# 05_LMS7002M_Misc.net
KiCad netlist of a schematic drawn in Altium Designer
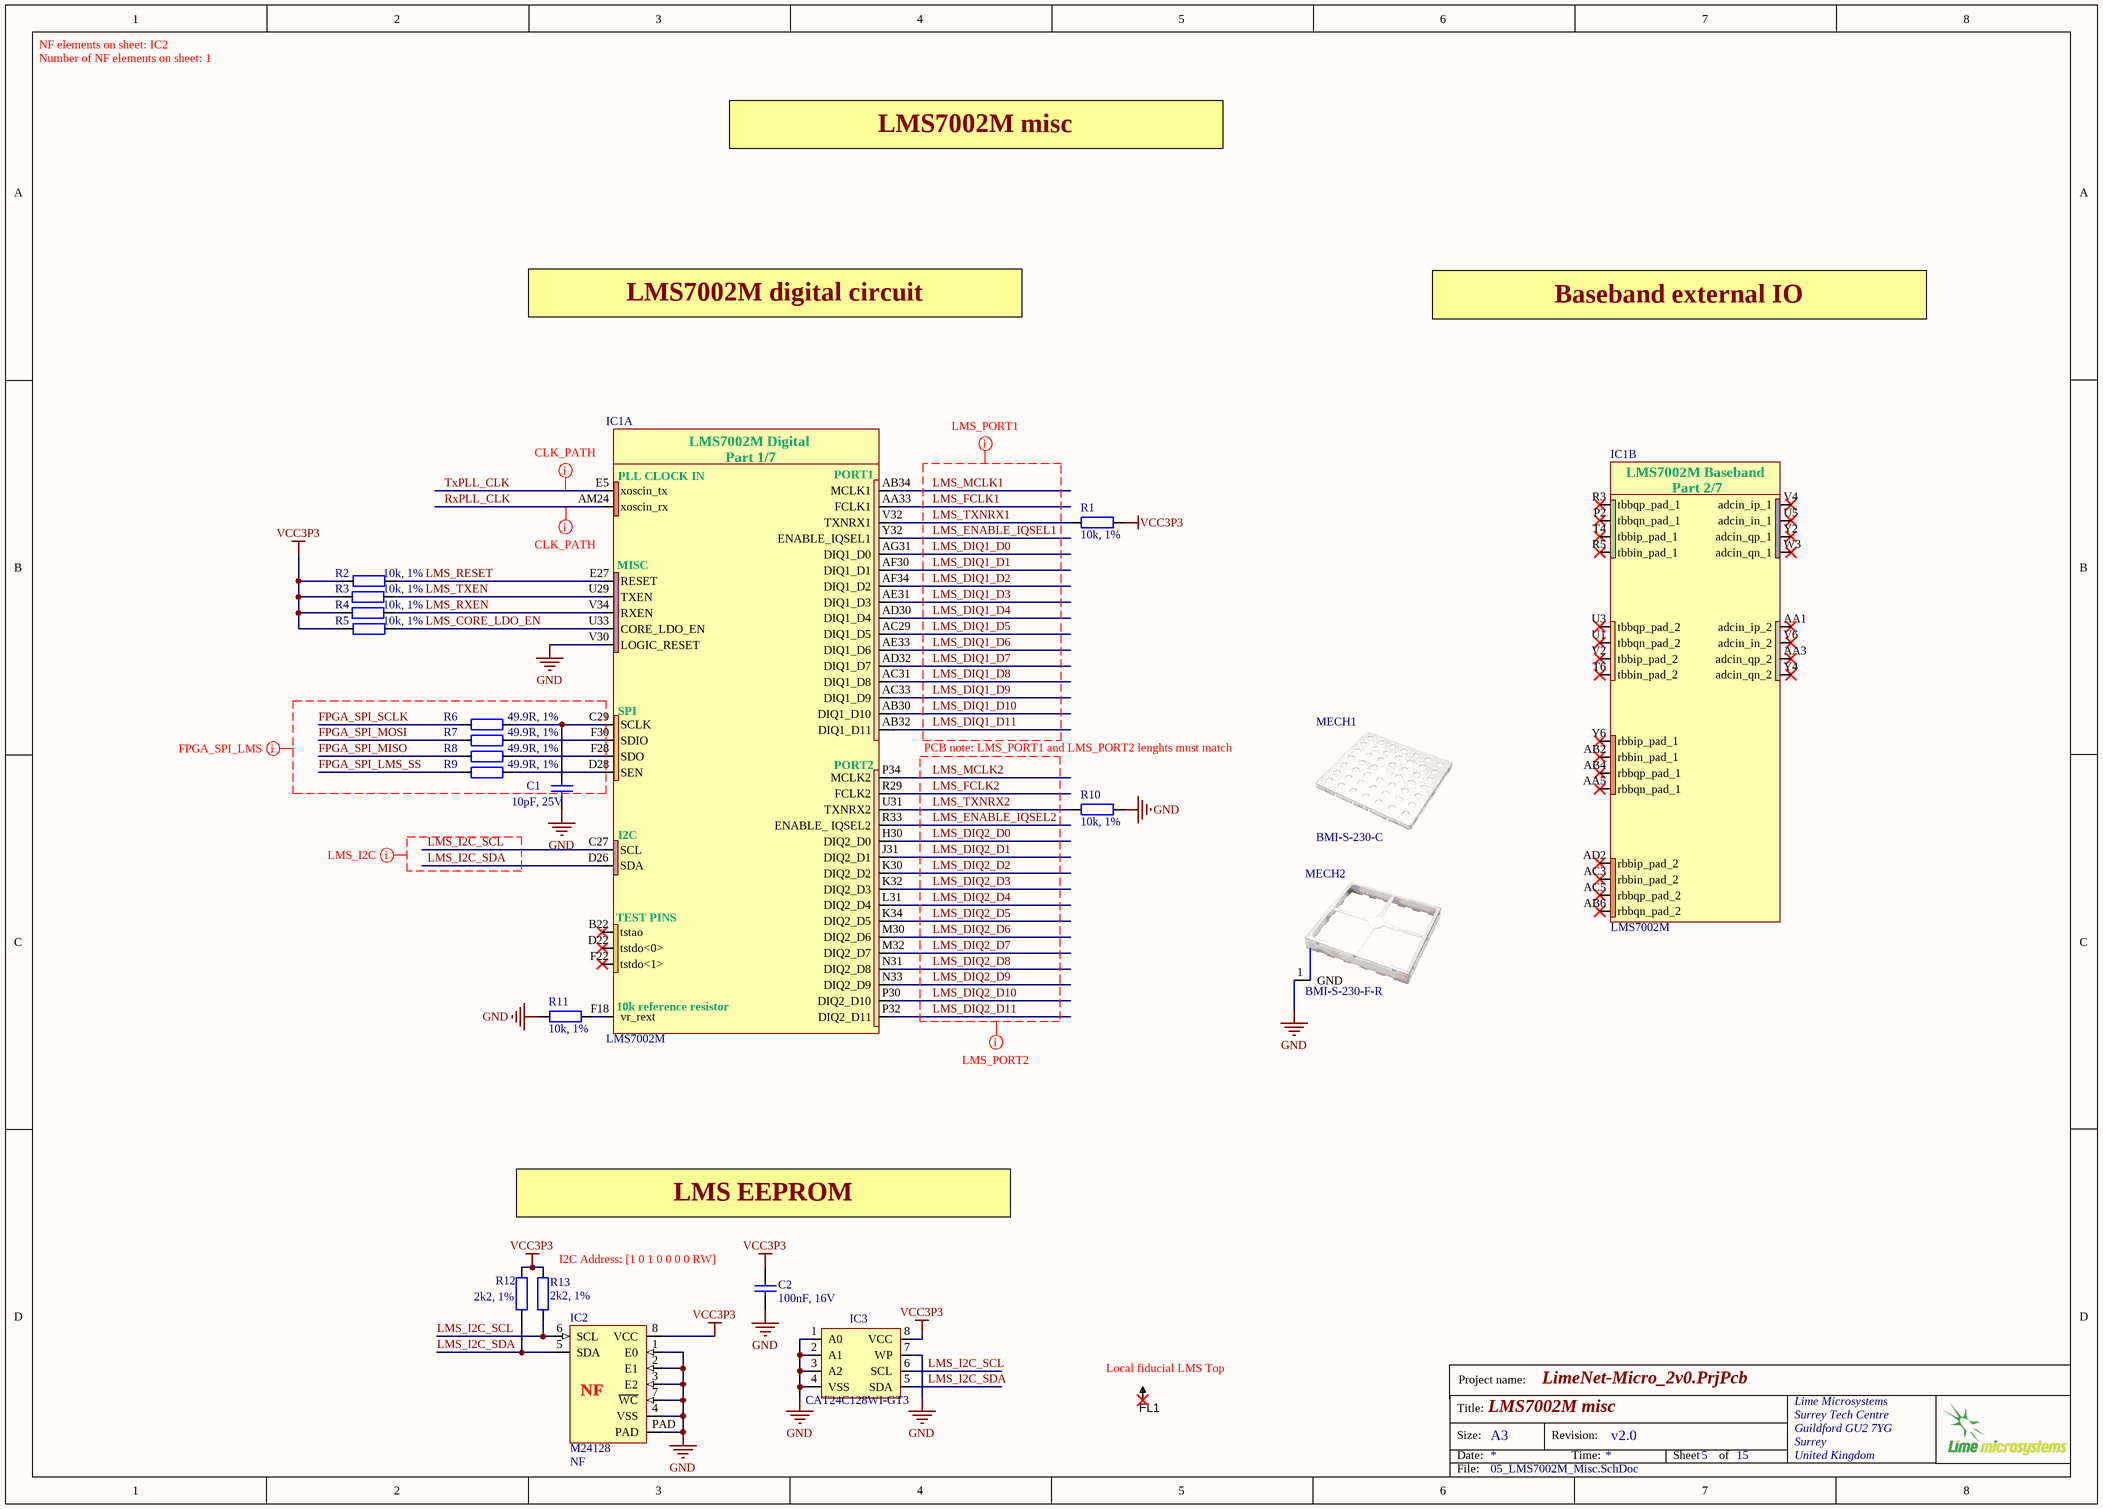
[diagram p0: 05_LMS7002M_Misc.SchDoc]

(export (version "E")
  (design (tool "Eeschema 10.0.6"))
  (components
    (comp (ref "C1")
      (value "10pF, 25V")
      (footprint "CAP0402")
      (fields (field (name "MANUFACTURER") "AVX"))
      (libsource (lib "LimeMicroAltiumLib_schLib") (part "Cap_0402"))
    )
    (comp (ref "C2")
      (value "100nF, 16V")
      (footprint "CAP0402")
      (fields (field (name "TOLERANCE") "10 %") (field (name "MANUFACTURER") "Murata Electronics"))
      (libsource (lib "LimeFPGAboard_schLib") (part "Cap_0603"))
    )
    (comp (ref "FL1")
      (value "Fiducial")
      (footprint "Fiducial_local")
      (libsource (lib "VGTU_Altium_lib") (part "Fiducial"))
    )
    (comp (ref "IC1")
      (value "LMS7002M")
      (footprint "LMS7002M_v5")
      (description "Schematic symbol revision 3. Default footprint - 0.31mm pad")
      (fields (field (name "MANUFACTURER") "Lime Microsystems"))
      (libsource (lib "LimeMicroAltiumLib_schLib") (part "LMS7002Mr3"))
    )
    (comp (ref "IC2")
      (value "M24128")
      (footprint "M24128-DFMC6TG")
      (fields (field (name "MANUFACTURER") "STMicroelectronics") (field (name "ASSEMBLY INFO") "NF"))
      (libsource (lib "LimeMicroAltiumLib_schLib") (part "M24128-DFMC6TG"))
    )
    (comp (ref "IC3")
      (value "CAT24C128WI-GT3")
      (footprint "SOIC127P600-8DL_v2")
      (fields (field (name "MANUFACTURER") "ON Semiconductor") (field (name "BASE PART NUMBER") "CAT24C128"))
      (libsource (lib "LimeMicroAltiumLib_schLib") (part "24FC64F"))
    )
    (comp (ref "MECH1")
      (value "BMI-S-230-C")
      (fields (field (name "MANUFACTURER") "Laird Technologies EMI"))
      (libsource (lib "LimeMicroAltiumLib_schLib_r01") (part "RFI_SHIELD_2_cover"))
    )
    (comp (ref "MECH2")
      (value "BMI-S-230-F-R")
      (footprint "RFI_SHIELD_BMI-S-230-F-R")
      (fields (field (name "MANUFACTURER") "Laird Technologies EMI"))
      (libsource (lib "LimeMicroAltiumLib_schLib_r01") (part "RFI_SHIELD_2_frame"))
    )
    (comp (ref "R1")
      (value "10k, 1%")
      (footprint "RES0402")
      (fields (field (name "MANUFACTURER") "Yageo") (field (name "TOLERANCE") "±1%"))
      (libsource (lib "LimeMicroAltiumLib_schLib") (part "Res_0402"))
    )
    (comp (ref "R2")
      (value "10k, 1%")
      (footprint "RES0402")
      (fields (field (name "MANUFACTURER") "Yageo") (field (name "TOLERANCE") "±1%"))
      (libsource (lib "LimeMicroAltiumLib_schLib") (part "Res_0402"))
    )
    (comp (ref "R3")
      (value "10k, 1%")
      (footprint "RES0402")
      (fields (field (name "MANUFACTURER") "Yageo") (field (name "TOLERANCE") "±1%"))
      (libsource (lib "LimeMicroAltiumLib_schLib") (part "Res_0402"))
    )
    (comp (ref "R4")
      (value "10k, 1%")
      (footprint "RES0402")
      (fields (field (name "MANUFACTURER") "Yageo") (field (name "TOLERANCE") "±1%"))
      (libsource (lib "LimeMicroAltiumLib_schLib") (part "Res_0402"))
    )
    (comp (ref "R5")
      (value "10k, 1%")
      (footprint "RES0402")
      (fields (field (name "MANUFACTURER") "Yageo") (field (name "TOLERANCE") "±1%"))
      (libsource (lib "LimeMicroAltiumLib_schLib") (part "Res_0402"))
    )
    (comp (ref "R6")
      (value "49.9R, 1%")
      (footprint "RES0402")
      (fields
        (field (name "TOLERANCE") "±1%")
        (field (name "MANUFACTURER") "Samsung Electro-Mechanics America, Inc.")
        (field (name "MANUFACTURER PART NUMBER") "RC1005F49R9CS")
      )
      (libsource (lib "LimeMicroAltiumLib_schLib") (part "Res_0402"))
    )
    (comp (ref "R7")
      (value "49.9R, 1%")
      (footprint "RES0402")
      (fields
        (field (name "TOLERANCE") "±1%")
        (field (name "MANUFACTURER") "Samsung Electro-Mechanics America, Inc.")
        (field (name "MANUFACTURER PART NUMBER") "RC1005F49R9CS")
      )
      (libsource (lib "LimeMicroAltiumLib_schLib") (part "Res_0402"))
    )
    (comp (ref "R8")
      (value "49.9R, 1%")
      (footprint "RES0402")
      (fields
        (field (name "TOLERANCE") "±1%")
        (field (name "MANUFACTURER") "Samsung Electro-Mechanics America, Inc.")
        (field (name "MANUFACTURER PART NUMBER") "RC1005F49R9CS")
      )
      (libsource (lib "LimeMicroAltiumLib_schLib") (part "Res_0402"))
    )
    (comp (ref "R9")
      (value "49.9R, 1%")
      (footprint "RES0402")
      (fields
        (field (name "TOLERANCE") "±1%")
        (field (name "MANUFACTURER") "Samsung Electro-Mechanics America, Inc.")
        (field (name "MANUFACTURER PART NUMBER") "RC1005F49R9CS")
      )
      (libsource (lib "LimeMicroAltiumLib_schLib") (part "Res_0402"))
    )
    (comp (ref "R10")
      (value "10k, 1%")
      (footprint "RES0402")
      (fields (field (name "MANUFACTURER") "Yageo") (field (name "TOLERANCE") "±1%"))
      (libsource (lib "LimeMicroAltiumLib_schLib") (part "Res_0402"))
    )
    (comp (ref "R11")
      (value "10k, 1%")
      (footprint "RES0402")
      (fields (field (name "MANUFACTURER") "Yageo") (field (name "TOLERANCE") "±1%"))
      (libsource (lib "LimeMicroAltiumLib_schLib") (part "Res_0402"))
    )
    (comp (ref "R12")
      (value "2k2, 1%")
      (footprint "RES0402")
      (fields (field (name "MANUFACTURER") "Stackpole Electronics Inc") (field (name "TOLERANCE") "±1%"))
      (libsource (lib "LimeMicroAltiumLib_schLib") (part "Res_0402"))
    )
    (comp (ref "R13")
      (value "2k2, 1%")
      (footprint "RES0402")
      (fields (field (name "MANUFACTURER") "Stackpole Electronics Inc") (field (name "TOLERANCE") "±1%"))
      (libsource (lib "LimeMicroAltiumLib_schLib") (part "Res_0402"))
    )
  )
  (nets
    (net (code "1") (name "/FPGA_SPI_LMS_SS") (class "Default")
      (node (ref "R9") (pin "2") (pinfunction "2_2") (pintype "passive"))
    )
    (net (code "2") (name "/FPGA_SPI_MISO") (class "Default")
      (node (ref "R8") (pin "2") (pinfunction "2_2") (pintype "passive"))
    )
    (net (code "3") (name "/FPGA_SPI_MOSI") (class "Default")
      (node (ref "R7") (pin "2") (pinfunction "2_2") (pintype "passive"))
    )
    (net (code "4") (name "/FPGA_SPI_SCLK") (class "Default")
      (node (ref "R6") (pin "2") (pinfunction "2_2") (pintype "passive"))
    )
    (net (code "5") (name "/LMS_CORE_LDO_EN") (class "Default")
      (node (ref "IC1") (pin "U33") (pinfunction "CORE_LDO_EN_U33") (pintype "passive"))
      (node (ref "R5") (pin "1") (pinfunction "1_1") (pintype "passive"))
    )
    (net (code "6") (name "/LMS_DIQ1_D0") (class "Default")
      (node (ref "IC1") (pin "AG31") (pinfunction "DIQ1_D0_AG31") (pintype "passive"))
    )
    (net (code "7") (name "/LMS_DIQ1_D1") (class "Default")
      (node (ref "IC1") (pin "AF30") (pinfunction "DIQ1_D1_AF30") (pintype "passive"))
    )
    (net (code "8") (name "/LMS_DIQ1_D2") (class "Default")
      (node (ref "IC1") (pin "AF34") (pinfunction "DIQ1_D2_AF34") (pintype "passive"))
    )
    (net (code "9") (name "/LMS_DIQ1_D3") (class "Default")
      (node (ref "IC1") (pin "AE31") (pinfunction "DIQ1_D3_AE31") (pintype "passive"))
    )
    (net (code "10") (name "/LMS_DIQ1_D4") (class "Default")
      (node (ref "IC1") (pin "AD30") (pinfunction "DIQ1_D4_AD30") (pintype "passive"))
    )
    (net (code "11") (name "/LMS_DIQ1_D5") (class "Default")
      (node (ref "IC1") (pin "AC29") (pinfunction "DIQ1_D5_AC29") (pintype "passive"))
    )
    (net (code "12") (name "/LMS_DIQ1_D6") (class "Default")
      (node (ref "IC1") (pin "AE33") (pinfunction "DIQ1_D6_AE33") (pintype "passive"))
    )
    (net (code "13") (name "/LMS_DIQ1_D7") (class "Default")
      (node (ref "IC1") (pin "AD32") (pinfunction "DIQ1_D7_AD32") (pintype "passive"))
    )
    (net (code "14") (name "/LMS_DIQ1_D8") (class "Default")
      (node (ref "IC1") (pin "AC31") (pinfunction "DIQ1_D8_AC31") (pintype "passive"))
    )
    (net (code "15") (name "/LMS_DIQ1_D9") (class "Default")
      (node (ref "IC1") (pin "AC33") (pinfunction "DIQ1_D9_AC33") (pintype "passive"))
    )
    (net (code "16") (name "/LMS_DIQ1_D10") (class "Default")
      (node (ref "IC1") (pin "AB30") (pinfunction "DIQ1_D10_AB30") (pintype "passive"))
    )
    (net (code "17") (name "/LMS_DIQ1_D11") (class "Default")
      (node (ref "IC1") (pin "AB32") (pinfunction "DIQ1_D11_AB32") (pintype "passive"))
    )
    (net (code "18") (name "/LMS_DIQ2_D0") (class "Default")
      (node (ref "IC1") (pin "H30") (pinfunction "DIQ2_D0_H30") (pintype "passive"))
    )
    (net (code "19") (name "/LMS_DIQ2_D1") (class "Default")
      (node (ref "IC1") (pin "J31") (pinfunction "DIQ2_D1_J31") (pintype "passive"))
    )
    (net (code "20") (name "/LMS_DIQ2_D2") (class "Default")
      (node (ref "IC1") (pin "K30") (pinfunction "DIQ2_D2_K30") (pintype "passive"))
    )
    (net (code "21") (name "/LMS_DIQ2_D3") (class "Default")
      (node (ref "IC1") (pin "K32") (pinfunction "DIQ2_D3_K32") (pintype "passive"))
    )
    (net (code "22") (name "/LMS_DIQ2_D4") (class "Default")
      (node (ref "IC1") (pin "L31") (pinfunction "DIQ2_D4_L31") (pintype "passive"))
    )
    (net (code "23") (name "/LMS_DIQ2_D5") (class "Default")
      (node (ref "IC1") (pin "K34") (pinfunction "DIQ2_D5_K34") (pintype "passive"))
    )
    (net (code "24") (name "/LMS_DIQ2_D6") (class "Default")
      (node (ref "IC1") (pin "M30") (pinfunction "DIQ2_D6_M30") (pintype "passive"))
    )
    (net (code "25") (name "/LMS_DIQ2_D7") (class "Default")
      (node (ref "IC1") (pin "M32") (pinfunction "DIQ2_D7_M32") (pintype "passive"))
    )
    (net (code "26") (name "/LMS_DIQ2_D8") (class "Default")
      (node (ref "IC1") (pin "N31") (pinfunction "DIQ2_D8_N31") (pintype "passive"))
    )
    (net (code "27") (name "/LMS_DIQ2_D9") (class "Default")
      (node (ref "IC1") (pin "N33") (pinfunction "DIQ2_D9_N33") (pintype "passive"))
    )
    (net (code "28") (name "/LMS_DIQ2_D10") (class "Default")
      (node (ref "IC1") (pin "P30") (pinfunction "DIQ2_D10_P30") (pintype "passive"))
    )
    (net (code "29") (name "/LMS_DIQ2_D11") (class "Default")
      (node (ref "IC1") (pin "P32") (pinfunction "DIQ2_D11_P32") (pintype "passive"))
    )
    (net (code "30") (name "/LMS_ENABLE_IQSEL1") (class "Default")
      (node (ref "IC1") (pin "Y32") (pinfunction "ENABLE_IQSEL1_Y32") (pintype "passive"))
    )
    (net (code "31") (name "/LMS_ENABLE_IQSEL2") (class "Default")
      (node (ref "IC1") (pin "R33") (pinfunction "ENABLE__IQSEL2_R33") (pintype "passive"))
    )
    (net (code "32") (name "/LMS_FCLK1") (class "Default")
      (node (ref "IC1") (pin "AA33") (pinfunction "FCLK1_AA33") (pintype "passive"))
    )
    (net (code "33") (name "/LMS_FCLK2") (class "Default")
      (node (ref "IC1") (pin "R29") (pinfunction "FCLK2_R29") (pintype "passive"))
    )
    (net (code "34") (name "/LMS_I2C_SCL") (class "Default")
      (node (ref "IC1") (pin "C27") (pinfunction "SCL_C27") (pintype "passive"))
      (node (ref "IC2") (pin "6") (pinfunction "SCL_6") (pintype "input"))
      (node (ref "IC3") (pin "6") (pinfunction "SCL_6") (pintype "passive"))
      (node (ref "R13") (pin "2") (pinfunction "2_2") (pintype "passive"))
    )
    (net (code "35") (name "/LMS_I2C_SDA") (class "Default")
      (node (ref "IC1") (pin "D26") (pinfunction "SDA_D26") (pintype "passive"))
      (node (ref "IC2") (pin "5") (pinfunction "SDA_5") (pintype "bidirectional"))
      (node (ref "IC3") (pin "5") (pinfunction "SDA_5") (pintype "passive"))
      (node (ref "R12") (pin "2") (pinfunction "2_2") (pintype "passive"))
    )
    (net (code "36") (name "/LMS_MCLK1") (class "Default")
      (node (ref "IC1") (pin "AB34") (pinfunction "MCLK1_AB34") (pintype "passive"))
    )
    (net (code "37") (name "/LMS_MCLK2") (class "Default")
      (node (ref "IC1") (pin "P34") (pinfunction "MCLK2_P34") (pintype "passive"))
    )
    (net (code "38") (name "/LMS_RESET") (class "Default")
      (node (ref "IC1") (pin "E27") (pinfunction "RESET_E27") (pintype "passive"))
      (node (ref "R2") (pin "1") (pinfunction "1_1") (pintype "passive"))
    )
    (net (code "39") (name "/LMS_RXEN") (class "Default")
      (node (ref "IC1") (pin "V34") (pinfunction "RXEN_V34") (pintype "passive"))
      (node (ref "R4") (pin "2") (pinfunction "2_2") (pintype "passive"))
    )
    (net (code "40") (name "/LMS_TXEN") (class "Default")
      (node (ref "IC1") (pin "U29") (pinfunction "TXEN_U29") (pintype "passive"))
      (node (ref "R3") (pin "2") (pinfunction "2_2") (pintype "passive"))
    )
    (net (code "41") (name "/LMS_TXNRX1") (class "Default")
      (node (ref "IC1") (pin "V32") (pinfunction "TXNRX1_V32") (pintype "passive"))
      (node (ref "R1") (pin "1") (pinfunction "1_1") (pintype "passive"))
    )
    (net (code "42") (name "/LMS_TXNRX2") (class "Default")
      (node (ref "IC1") (pin "U31") (pinfunction "TXNRX2_U31") (pintype "passive"))
      (node (ref "R10") (pin "1") (pinfunction "1_1") (pintype "passive"))
    )
    (net (code "43") (name "/RxPLL_CLK") (class "Default")
      (node (ref "IC1") (pin "AM24") (pinfunction "xoscin_rx_AM24") (pintype "passive"))
    )
    (net (code "44") (name "/TxPLL_CLK") (class "Default")
      (node (ref "IC1") (pin "E5") (pinfunction "xoscin_tx_E5") (pintype "passive"))
    )
    (net (code "45") (name "GND") (class "Default")
      (node (ref "C1") (pin "2") (pinfunction "2_2") (pintype "passive"))
      (node (ref "C2") (pin "2") (pinfunction "2_2") (pintype "passive"))
      (node (ref "IC1") (pin "V30") (pinfunction "LOGIC_RESET_V30") (pintype "passive"))
      (node (ref "IC2") (pin "1") (pinfunction "E0_1") (pintype "input"))
      (node (ref "IC2") (pin "2") (pinfunction "E1_2") (pintype "input"))
      (node (ref "IC2") (pin "3") (pinfunction "E2_3") (pintype "input"))
      (node (ref "IC2") (pin "4") (pinfunction "VSS_4") (pintype "power_in"))
      (node (ref "IC2") (pin "7") (pinfunction "~{WC}_7") (pintype "input"))
      (node (ref "IC2") (pin "PAD") (pinfunction "PAD_PAD") (pintype "power_in"))
      (node (ref "IC3") (pin "1") (pinfunction "A0_1") (pintype "passive"))
      (node (ref "IC3") (pin "2") (pinfunction "A1_2") (pintype "passive"))
      (node (ref "IC3") (pin "3") (pinfunction "A2_3") (pintype "passive"))
      (node (ref "IC3") (pin "4") (pinfunction "VSS_4") (pintype "passive"))
      (node (ref "IC3") (pin "7") (pinfunction "WP_7") (pintype "passive"))
      (node (ref "MECH2") (pin "1") (pinfunction "GND_1") (pintype "passive"))
      (node (ref "R10") (pin "2") (pinfunction "2_2") (pintype "passive"))
      (node (ref "R11") (pin "2") (pinfunction "2_2") (pintype "passive"))
    )
    (net (code "46") (name "Net-(IC1A-SCLK)") (class "Default")
      (node (ref "C1") (pin "1") (pinfunction "1_1") (pintype "passive"))
      (node (ref "IC1") (pin "C29") (pinfunction "SCLK_C29") (pintype "passive"))
      (node (ref "R6") (pin "1") (pinfunction "1_1") (pintype "passive"))
    )
    (net (code "47") (name "Net-(IC1A-SDIO)") (class "Default")
      (node (ref "IC1") (pin "F30") (pinfunction "SDIO_F30") (pintype "passive"))
      (node (ref "R7") (pin "1") (pinfunction "1_1") (pintype "passive"))
    )
    (net (code "48") (name "Net-(IC1A-SDO)") (class "Default")
      (node (ref "IC1") (pin "F28") (pinfunction "SDO_F28") (pintype "passive"))
      (node (ref "R8") (pin "1") (pinfunction "1_1") (pintype "passive"))
    )
    (net (code "49") (name "Net-(IC1A-SEN)") (class "Default")
      (node (ref "IC1") (pin "D28") (pinfunction "SEN_D28") (pintype "passive"))
      (node (ref "R9") (pin "1") (pinfunction "1_1") (pintype "passive"))
    )
    (net (code "50") (name "Net-(IC1A-vr_rext)") (class "Default")
      (node (ref "IC1") (pin "F18") (pinfunction "vr_rext_F18") (pintype "passive"))
      (node (ref "R11") (pin "1") (pinfunction "1_1") (pintype "passive"))
    )
    (net (code "51") (name "VCC3P3") (class "Default")
      (node (ref "C2") (pin "1") (pinfunction "1_1") (pintype "passive"))
      (node (ref "IC2") (pin "8") (pinfunction "VCC_8") (pintype "power_in"))
      (node (ref "IC3") (pin "8") (pinfunction "VCC_8") (pintype "passive"))
      (node (ref "R1") (pin "2") (pinfunction "2_2") (pintype "passive"))
      (node (ref "R12") (pin "1") (pinfunction "1_1") (pintype "passive"))
      (node (ref "R13") (pin "1") (pinfunction "1_1") (pintype "passive"))
      (node (ref "R2") (pin "2") (pinfunction "2_2") (pintype "passive"))
      (node (ref "R3") (pin "1") (pinfunction "1_1") (pintype "passive"))
      (node (ref "R4") (pin "1") (pinfunction "1_1") (pintype "passive"))
      (node (ref "R5") (pin "2") (pinfunction "2_2") (pintype "passive"))
    )
    (net (code "52") (name "unconnected-(FL1-Pad1)") (class "Default")
      (node (ref "FL1") (pin "1") (pintype "passive+no_connect"))
    )
    (net (code "53") (name "unconnected-(IC1A-tstao-PadB22)") (class "Default")
      (node (ref "IC1") (pin "B22") (pinfunction "tstao_B22") (pintype "passive+no_connect"))
    )
    (net (code "54") (name "unconnected-(IC1A-tstdo<0>-PadD22)") (class "Default")
      (node (ref "IC1") (pin "D22") (pinfunction "tstdo<0>_D22") (pintype "passive+no_connect"))
    )
    (net (code "55") (name "unconnected-(IC1A-tstdo<1>-PadF22)") (class "Default")
      (node (ref "IC1") (pin "F22") (pinfunction "tstdo<1>_F22") (pintype "passive+no_connect"))
    )
    (net (code "56") (name "unconnected-(IC1B-adcin_in_1-PadU5)") (class "Default")
      (node (ref "IC1") (pin "U5") (pinfunction "adcin_in_1_U5") (pintype "passive+no_connect"))
    )
    (net (code "57") (name "unconnected-(IC1B-adcin_in_2-PadV6)") (class "Default")
      (node (ref "IC1") (pin "V6") (pinfunction "adcin_in_2_V6") (pintype "passive+no_connect"))
    )
    (net (code "58") (name "unconnected-(IC1B-adcin_ip_1-PadV4)") (class "Default")
      (node (ref "IC1") (pin "V4") (pinfunction "adcin_ip_1_V4") (pintype "passive+no_connect"))
    )
    (net (code "59") (name "unconnected-(IC1B-adcin_ip_2-PadAA1)") (class "Default")
      (node (ref "IC1") (pin "AA1") (pinfunction "adcin_ip_2_AA1") (pintype "passive+no_connect"))
    )
    (net (code "60") (name "unconnected-(IC1B-adcin_qn_1-PadW3)") (class "Default")
      (node (ref "IC1") (pin "W3") (pinfunction "adcin_qn_1_W3") (pintype "passive+no_connect"))
    )
    (net (code "61") (name "unconnected-(IC1B-adcin_qn_2-PadY4)") (class "Default")
      (node (ref "IC1") (pin "Y4") (pinfunction "adcin_qn_2_Y4") (pintype "passive+no_connect"))
    )
    (net (code "62") (name "unconnected-(IC1B-adcin_qp_1-PadY2)") (class "Default")
      (node (ref "IC1") (pin "Y2") (pinfunction "adcin_qp_1_Y2") (pintype "passive+no_connect"))
    )
    (net (code "63") (name "unconnected-(IC1B-adcin_qp_2-PadAA3)") (class "Default")
      (node (ref "IC1") (pin "AA3") (pinfunction "adcin_qp_2_AA3") (pintype "passive+no_connect"))
    )
    (net (code "64") (name "unconnected-(IC1B-rbbin_pad_1-PadAB2)") (class "Default")
      (node (ref "IC1") (pin "AB2") (pinfunction "rbbin_pad_1_AB2") (pintype "passive+no_connect"))
    )
    (net (code "65") (name "unconnected-(IC1B-rbbin_pad_2-PadAC3)") (class "Default")
      (node (ref "IC1") (pin "AC3") (pinfunction "rbbin_pad_2_AC3") (pintype "passive+no_connect"))
    )
    (net (code "66") (name "unconnected-(IC1B-rbbip_pad_1-PadY6)") (class "Default")
      (node (ref "IC1") (pin "Y6") (pinfunction "rbbip_pad_1_Y6") (pintype "passive+no_connect"))
    )
    (net (code "67") (name "unconnected-(IC1B-rbbip_pad_2-PadAD2)") (class "Default")
      (node (ref "IC1") (pin "AD2") (pinfunction "rbbip_pad_2_AD2") (pintype "passive+no_connect"))
    )
    (net (code "68") (name "unconnected-(IC1B-rbbqn_pad_1-PadAA5)") (class "Default")
      (node (ref "IC1") (pin "AA5") (pinfunction "rbbqn_pad_1_AA5") (pintype "passive+no_connect"))
    )
    (net (code "69") (name "unconnected-(IC1B-rbbqn_pad_2-PadAB6)") (class "Default")
      (node (ref "IC1") (pin "AB6") (pinfunction "rbbqn_pad_2_AB6") (pintype "passive+no_connect"))
    )
    (net (code "70") (name "unconnected-(IC1B-rbbqp_pad_1-PadAB4)") (class "Default")
      (node (ref "IC1") (pin "AB4") (pinfunction "rbbqp_pad_1_AB4") (pintype "passive+no_connect"))
    )
    (net (code "71") (name "unconnected-(IC1B-rbbqp_pad_2-PadAC5)") (class "Default")
      (node (ref "IC1") (pin "AC5") (pinfunction "rbbqp_pad_2_AC5") (pintype "passive+no_connect"))
    )
    (net (code "72") (name "unconnected-(IC1B-tbbin_pad_1-PadR5)") (class "Default")
      (node (ref "IC1") (pin "R5") (pinfunction "tbbin_pad_1_R5") (pintype "passive+no_connect"))
    )
    (net (code "73") (name "unconnected-(IC1B-tbbin_pad_2-PadT6)") (class "Default")
      (node (ref "IC1") (pin "T6") (pinfunction "tbbin_pad_2_T6") (pintype "passive+no_connect"))
    )
    (net (code "74") (name "unconnected-(IC1B-tbbip_pad_1-PadT4)") (class "Default")
      (node (ref "IC1") (pin "T4") (pinfunction "tbbip_pad_1_T4") (pintype "passive+no_connect"))
    )
    (net (code "75") (name "unconnected-(IC1B-tbbip_pad_2-PadV2)") (class "Default")
      (node (ref "IC1") (pin "V2") (pinfunction "tbbip_pad_2_V2") (pintype "passive+no_connect"))
    )
    (net (code "76") (name "unconnected-(IC1B-tbbqn_pad_1-PadP2)") (class "Default")
      (node (ref "IC1") (pin "P2") (pinfunction "tbbqn_pad_1_P2") (pintype "passive+no_connect"))
    )
    (net (code "77") (name "unconnected-(IC1B-tbbqn_pad_2-PadU1)") (class "Default")
      (node (ref "IC1") (pin "U1") (pinfunction "tbbqn_pad_2_U1") (pintype "passive+no_connect"))
    )
    (net (code "78") (name "unconnected-(IC1B-tbbqp_pad_1-PadR3)") (class "Default")
      (node (ref "IC1") (pin "R3") (pinfunction "tbbqp_pad_1_R3") (pintype "passive+no_connect"))
    )
    (net (code "79") (name "unconnected-(IC1B-tbbqp_pad_2-PadU3)") (class "Default")
      (node (ref "IC1") (pin "U3") (pinfunction "tbbqp_pad_2_U3") (pintype "passive+no_connect"))
    )
  )
)
